# BLE-Modul.net
KiCad netlist of a schematic drawn in EAGLE
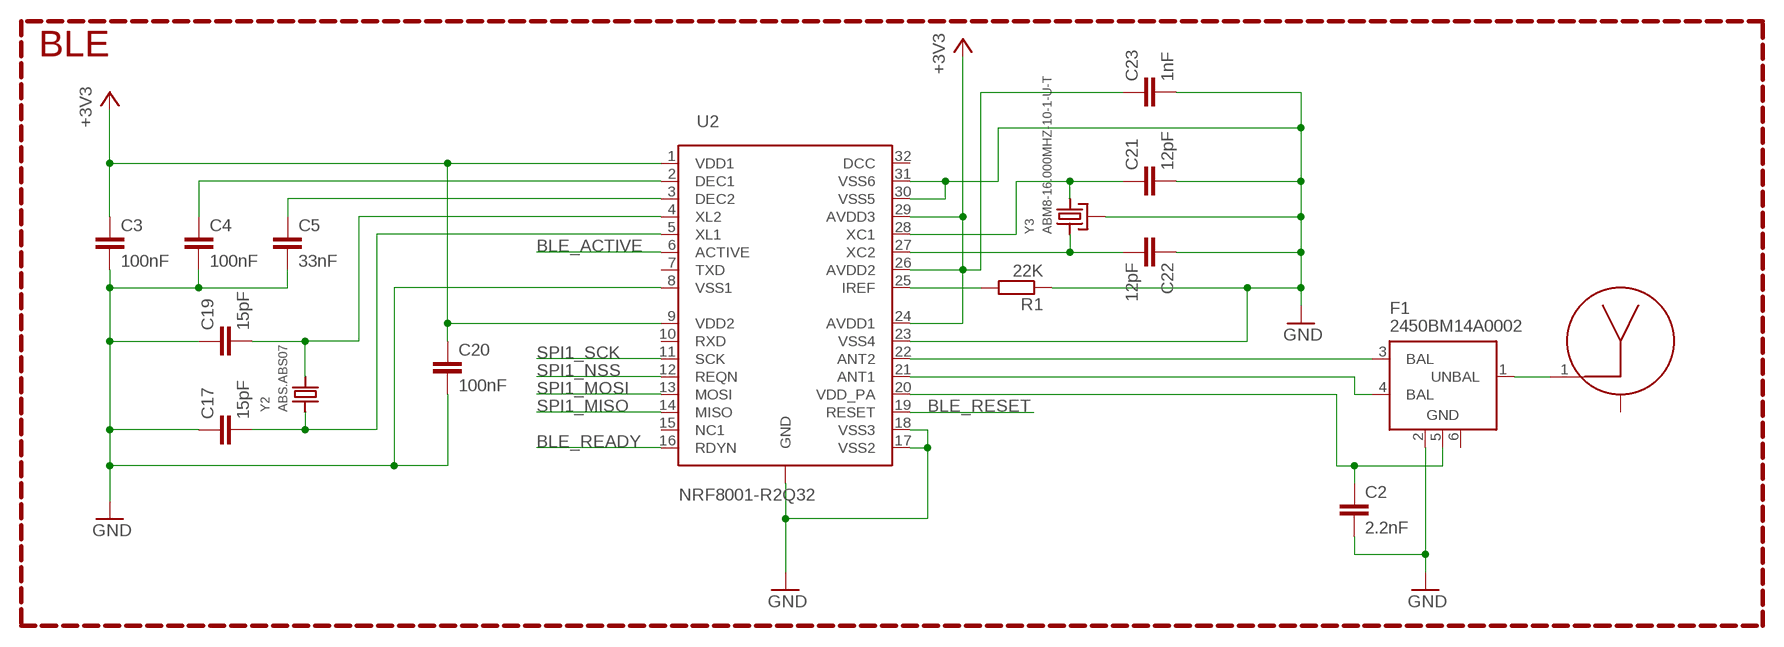
[diagram p0: schematic, sheet 1]

(export (version "E")
  (design (tool "Eeschema 10.0.6"))
  (components
    (comp (ref "A1")
      (value "2450AT18A100")
      (footprint "eagle-import:2450AT18A100E")
      (libsource (lib "eagle-import") (part "2450AT18A100"))
    )
    (comp (ref "C2")
      (value "2.2nF")
      (footprint "eagle-import:C0402K")
      (libsource (lib "eagle-import") (part "C-EUC0402K"))
    )
    (comp (ref "C3")
      (value "100nF")
      (footprint "eagle-import:C0402K")
      (libsource (lib "eagle-import") (part "C-EUC0402K"))
    )
    (comp (ref "C4")
      (value "100nF")
      (footprint "eagle-import:C0402K")
      (libsource (lib "eagle-import") (part "C-EUC0402K"))
    )
    (comp (ref "C5")
      (value "33nF")
      (footprint "eagle-import:C0402K")
      (libsource (lib "eagle-import") (part "C-EUC0402K"))
    )
    (comp (ref "C17")
      (value "15pF")
      (footprint "eagle-import:C0402K")
      (libsource (lib "eagle-import") (part "C-EUC0402K"))
    )
    (comp (ref "C19")
      (value "15pF")
      (footprint "eagle-import:C0402K")
      (libsource (lib "eagle-import") (part "C-EUC0402K"))
    )
    (comp (ref "C20")
      (value "100nF")
      (footprint "eagle-import:C0402K")
      (libsource (lib "eagle-import") (part "C-EUC0402K"))
    )
    (comp (ref "C21")
      (value "12pF")
      (footprint "eagle-import:C0402K")
      (libsource (lib "eagle-import") (part "C-EUC0402K"))
    )
    (comp (ref "C22")
      (value "12pF")
      (footprint "eagle-import:C0402K")
      (libsource (lib "eagle-import") (part "C-EUC0402K"))
    )
    (comp (ref "C23")
      (value "1nF")
      (footprint "eagle-import:C0402K")
      (libsource (lib "eagle-import") (part "C-EUC0402K"))
    )
    (comp (ref "F1")
      (value "2450BM14A0002")
      (footprint "eagle-import:2450BM14A0002")
      (libsource (lib "eagle-import") (part "2450BM14A0002"))
    )
    (comp (ref "R1")
      (value "22K")
      (footprint "eagle-import:R0402")
      (libsource (lib "eagle-import") (part "R-EU_R0402"))
    )
    (comp (ref "U2")
      (value "NRF8001-R2Q32")
      (footprint "eagle-import:QFN32")
      (libsource (lib "eagle-import") (part "NRF8001-R2Q32"))
    )
    (comp (ref "Y2")
      (value "ABS.ABS07")
      (footprint "eagle-import:ABS07")
      (libsource (lib "eagle-import") (part "ABS.ABS07"))
    )
    (comp (ref "Y3")
      (value "ABM8-16.000MHZ-10-1-U-T")
      (footprint "eagle-import:3.2X2.5MM")
      (libsource (lib "eagle-import") (part "ABM8-16.000MHZ-10-1-U-T"))
    )
  )
  (nets
    (net (code "1") (name "+3V3") (class "Default")
      (node (ref "C20") (pin "1") (pinfunction "1_1") (pintype "passive"))
      (node (ref "C23") (pin "1") (pinfunction "1_1") (pintype "passive"))
      (node (ref "C3") (pin "1") (pinfunction "1_1") (pintype "passive"))
      (node (ref "U2") (pin "1") (pinfunction "VDD1_1") (pintype "power_in"))
      (node (ref "U2") (pin "24") (pinfunction "AVDD1_24") (pintype "power_in"))
      (node (ref "U2") (pin "26") (pinfunction "AVDD2_26") (pintype "power_in"))
      (node (ref "U2") (pin "29") (pinfunction "AVDD3_29") (pintype "power_in"))
      (node (ref "U2") (pin "9") (pinfunction "VDD2_9") (pintype "power_in"))
    )
    (net (code "2") (name "/BLE_ACTIVE") (class "Default")
      (node (ref "U2") (pin "6") (pinfunction "ACTIVE_6") (pintype "output"))
    )
    (net (code "3") (name "/BLE_READY") (class "Default")
      (node (ref "U2") (pin "16") (pinfunction "RDYN_16") (pintype "output"))
    )
    (net (code "4") (name "/BLE_RESET") (class "Default")
      (node (ref "U2") (pin "19") (pinfunction "RESET_19") (pintype "input"))
    )
    (net (code "5") (name "/DCC") (class "Default")
      (node (ref "U2") (pin "32") (pinfunction "DCC_32") (pintype "power_in"))
    )
    (net (code "6") (name "/SPI1_MISO") (class "Default")
      (node (ref "U2") (pin "14") (pinfunction "MISO_14") (pintype "output"))
    )
    (net (code "7") (name "/SPI1_MOSI") (class "Default")
      (node (ref "U2") (pin "13") (pinfunction "MOSI_13") (pintype "input"))
    )
    (net (code "8") (name "/SPI1_NSS") (class "Default")
      (node (ref "U2") (pin "12") (pinfunction "REQN_12") (pintype "input"))
    )
    (net (code "9") (name "/SPI1_SCK") (class "Default")
      (node (ref "U2") (pin "11") (pinfunction "SCK_11") (pintype "input"))
    )
    (net (code "10") (name "GND") (class "Default")
      (node (ref "C17") (pin "1") (pinfunction "1_1") (pintype "passive"))
      (node (ref "C19") (pin "1") (pinfunction "1_1") (pintype "passive"))
      (node (ref "C2") (pin "2") (pinfunction "2_2") (pintype "passive"))
      (node (ref "C20") (pin "2") (pinfunction "2_2") (pintype "passive"))
      (node (ref "C21") (pin "2") (pinfunction "2_2") (pintype "passive"))
      (node (ref "C22") (pin "1") (pinfunction "1_1") (pintype "passive"))
      (node (ref "C23") (pin "2") (pinfunction "2_2") (pintype "passive"))
      (node (ref "C3") (pin "2") (pinfunction "2_2") (pintype "passive"))
      (node (ref "C4") (pin "2") (pinfunction "2_2") (pintype "passive"))
      (node (ref "C5") (pin "2") (pinfunction "2_2") (pintype "passive"))
      (node (ref "F1") (pin "2") (pinfunction "GND_2") (pintype "passive"))
      (node (ref "R1") (pin "1") (pinfunction "1_1") (pintype "passive"))
      (node (ref "U2") (pin "17") (pinfunction "VSS2_17") (pintype "power_in"))
      (node (ref "U2") (pin "18") (pinfunction "VSS3_18") (pintype "power_in"))
      (node (ref "U2") (pin "23") (pinfunction "VSS4_23") (pintype "power_in"))
      (node (ref "U2") (pin "30") (pinfunction "VSS5_30") (pintype "power_in"))
      (node (ref "U2") (pin "31") (pinfunction "VSS6_31") (pintype "power_in"))
      (node (ref "U2") (pin "8") (pinfunction "VSS1_8") (pintype "power_in"))
      (node (ref "U2") (pin "P$1") (pinfunction "GND_P$1") (pintype "power_in"))
      (node (ref "Y3") (pin "2") (pinfunction "GND_2") (pintype "passive"))
      (node (ref "Y3") (pin "4") (pinfunction "GND_4") (pintype "passive"))
    )
    (net (code "11") (name "Net-(F1-UNBAL)") (class "Default")
      (node (ref "A1") (pin "1") (pinfunction "1_1") (pintype "bidirectional"))
      (node (ref "F1") (pin "1") (pinfunction "UNBAL_1") (pintype "passive"))
    )
    (net (code "12") (name "Net-(U2-ANT1)") (class "Default")
      (node (ref "F1") (pin "4") (pinfunction "BAL_4") (pintype "passive"))
      (node (ref "U2") (pin "21") (pinfunction "ANT1_21") (pintype "bidirectional"))
    )
    (net (code "13") (name "Net-(U2-ANT2)") (class "Default")
      (node (ref "F1") (pin "3") (pinfunction "BAL_3") (pintype "passive"))
      (node (ref "U2") (pin "22") (pinfunction "ANT2_22") (pintype "bidirectional"))
    )
    (net (code "14") (name "Net-(U2-DEC1)") (class "Default")
      (node (ref "C4") (pin "1") (pinfunction "1_1") (pintype "passive"))
      (node (ref "U2") (pin "2") (pinfunction "DEC1_2") (pintype "power_in"))
    )
    (net (code "15") (name "Net-(U2-DEC2)") (class "Default")
      (node (ref "C5") (pin "1") (pinfunction "1_1") (pintype "passive"))
      (node (ref "U2") (pin "3") (pinfunction "DEC2_3") (pintype "power_in"))
    )
    (net (code "16") (name "Net-(U2-IREF)") (class "Default")
      (node (ref "R1") (pin "2") (pinfunction "2_2") (pintype "passive"))
      (node (ref "U2") (pin "25") (pinfunction "IREF_25") (pintype "output"))
    )
    (net (code "17") (name "Net-(U2-VDD_PA)") (class "Default")
      (node (ref "C2") (pin "1") (pinfunction "1_1") (pintype "passive"))
      (node (ref "F1") (pin "5") (pinfunction "GND_5") (pintype "passive"))
      (node (ref "U2") (pin "20") (pinfunction "VDD_PA_20") (pintype "power_in"))
    )
    (net (code "18") (name "Net-(U2-XC1)") (class "Default")
      (node (ref "C21") (pin "1") (pinfunction "1_1") (pintype "passive"))
      (node (ref "U2") (pin "28") (pinfunction "XC1_28") (pintype "input"))
      (node (ref "Y3") (pin "3") (pinfunction "2_3") (pintype "passive"))
    )
    (net (code "19") (name "Net-(U2-XC2)") (class "Default")
      (node (ref "C22") (pin "2") (pinfunction "2_2") (pintype "passive"))
      (node (ref "U2") (pin "27") (pinfunction "XC2_27") (pintype "output"))
      (node (ref "Y3") (pin "1") (pinfunction "1_1") (pintype "passive"))
    )
    (net (code "20") (name "Net-(U2-XL1)") (class "Default")
      (node (ref "C17") (pin "2") (pinfunction "2_2") (pintype "passive"))
      (node (ref "U2") (pin "5") (pinfunction "XL1_5") (pintype "input"))
      (node (ref "Y2") (pin "1") (pinfunction "1_1") (pintype "passive"))
    )
    (net (code "21") (name "Net-(U2-XL2)") (class "Default")
      (node (ref "C19") (pin "2") (pinfunction "2_2") (pintype "passive"))
      (node (ref "U2") (pin "4") (pinfunction "XL2_4") (pintype "output"))
      (node (ref "Y2") (pin "2") (pinfunction "2_2") (pintype "passive"))
    )
    (net (code "22") (name "unconnected-(A1-Pad2)") (class "Default")
      (node (ref "A1") (pin "2") (pinfunction "2_2") (pintype "bidirectional"))
    )
    (net (code "23") (name "unconnected-(F1-GND-Pad6)") (class "Default")
      (node (ref "F1") (pin "6") (pinfunction "GND_6") (pintype "passive"))
    )
    (net (code "24") (name "unconnected-(U2-NC1-Pad15)") (class "Default")
      (node (ref "U2") (pin "15") (pinfunction "NC1_15") (pintype "no_connect"))
    )
    (net (code "25") (name "unconnected-(U2-RXD-Pad10)") (class "Default")
      (node (ref "U2") (pin "10") (pinfunction "RXD_10") (pintype "input"))
    )
    (net (code "26") (name "unconnected-(U2-TXD-Pad7)") (class "Default")
      (node (ref "U2") (pin "7") (pinfunction "TXD_7") (pintype "output"))
    )
  )
)
